# CadenceSense1_0.net
KiCad netlist of a schematic drawn in EAGLE
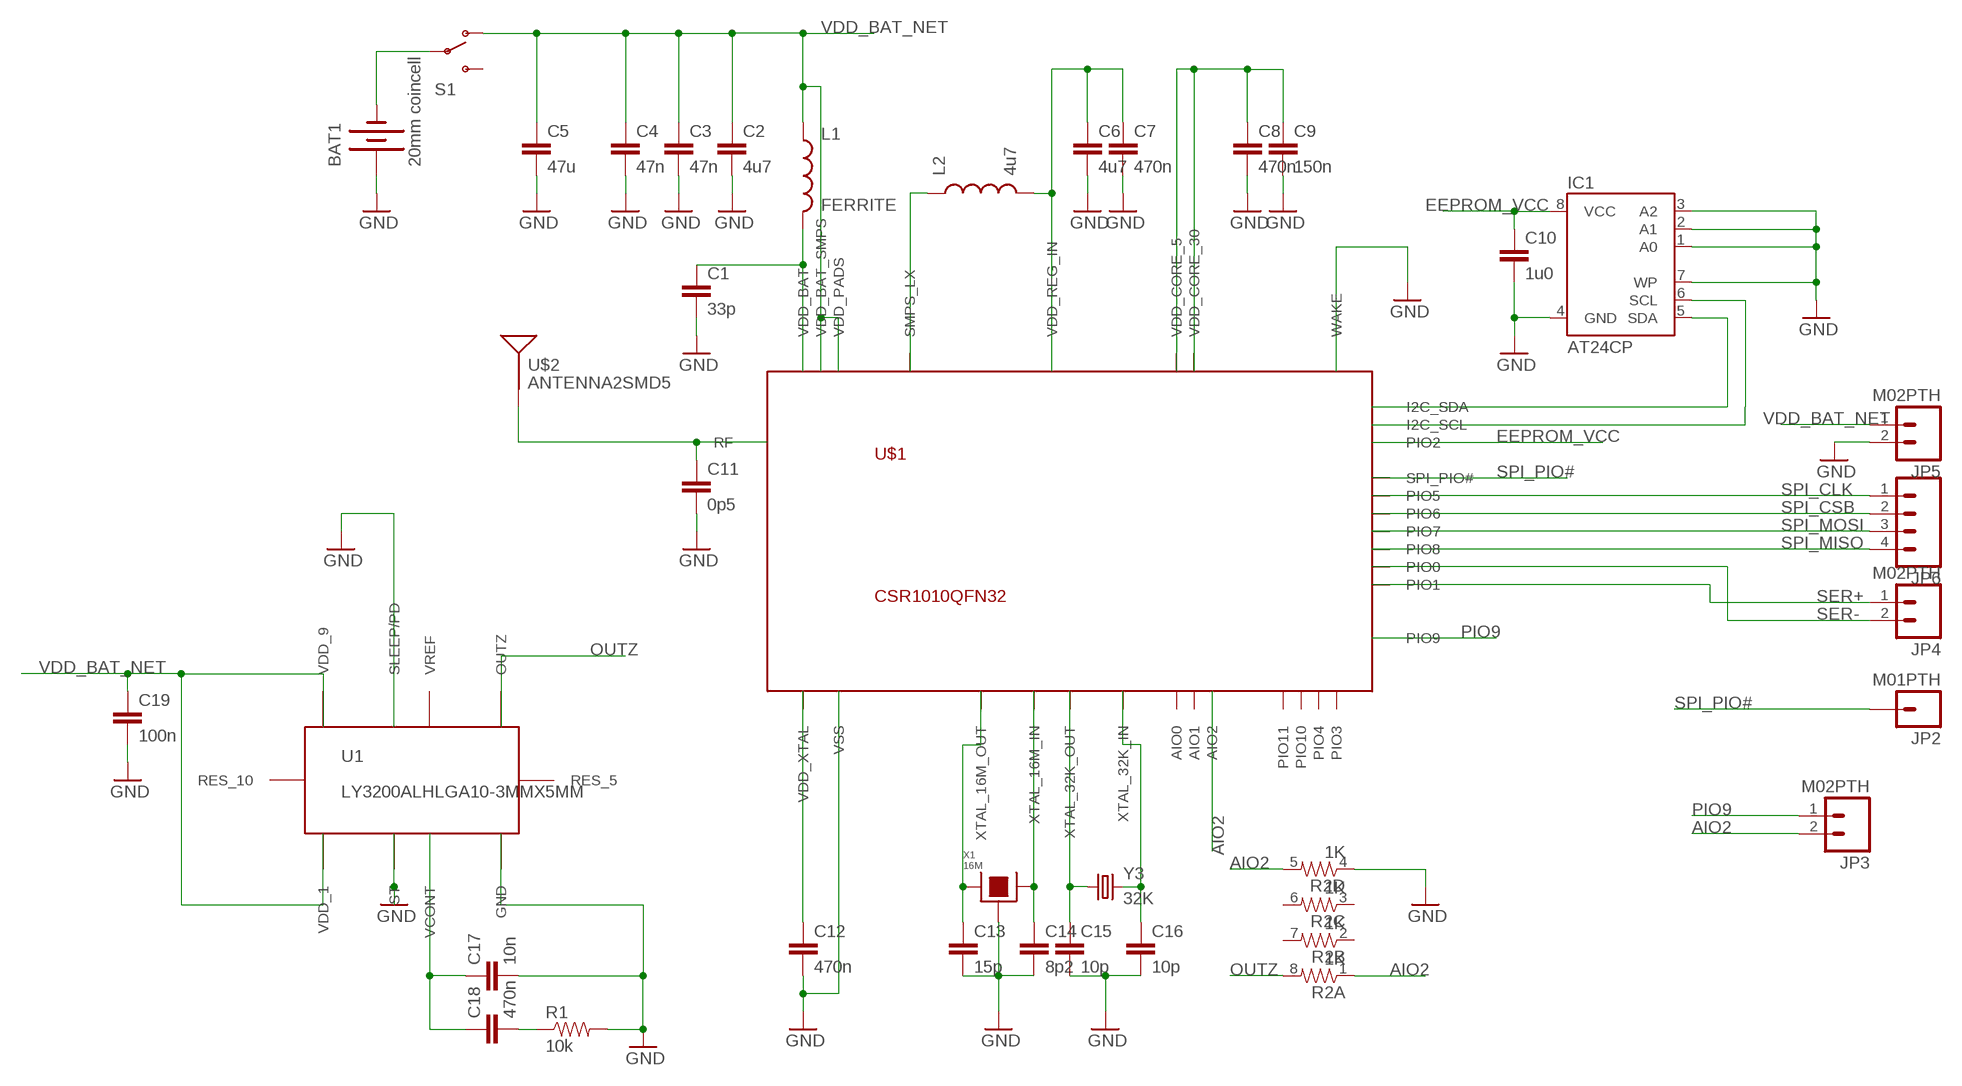
[diagram p0: schematic, sheet 1]

(export (version "E")
  (design (tool "Eeschema 10.0.6"))
  (components
    (comp (ref "BAT1")
      (value "20mm coincell")
      (footprint "eagle-import:BATTCON_20MM_4LEGS")
      (libsource (lib "eagle-import") (part "BATTERY20MM_4LEGS"))
    )
    (comp (ref "C1")
      (value "33p")
      (footprint "eagle-import:0603-CAP")
      (libsource (lib "eagle-import") (part "CAP0603-CAP"))
    )
    (comp (ref "C2")
      (value "4u7")
      (footprint "eagle-import:0603-CAP")
      (libsource (lib "eagle-import") (part "CAP0603-CAP"))
    )
    (comp (ref "C3")
      (value "47n")
      (footprint "eagle-import:0603-CAP")
      (libsource (lib "eagle-import") (part "CAP0603-CAP"))
    )
    (comp (ref "C4")
      (value "47n")
      (footprint "eagle-import:0603-CAP")
      (libsource (lib "eagle-import") (part "CAP0603-CAP"))
    )
    (comp (ref "C5")
      (value "47u")
      (footprint "eagle-import:0603-CAP")
      (libsource (lib "eagle-import") (part "CAP0603-CAP"))
    )
    (comp (ref "C6")
      (value "4u7")
      (footprint "eagle-import:0603-CAP")
      (libsource (lib "eagle-import") (part "CAP0603-CAP"))
    )
    (comp (ref "C7")
      (value "470n")
      (footprint "eagle-import:0603-CAP")
      (libsource (lib "eagle-import") (part "CAP0603-CAP"))
    )
    (comp (ref "C8")
      (value "470n")
      (footprint "eagle-import:0603-CAP")
      (libsource (lib "eagle-import") (part "CAP0603-CAP"))
    )
    (comp (ref "C9")
      (value "150n")
      (footprint "eagle-import:0603-CAP")
      (libsource (lib "eagle-import") (part "CAP0603-CAP"))
    )
    (comp (ref "C10")
      (value "1u0")
      (footprint "eagle-import:0603-CAP")
      (libsource (lib "eagle-import") (part "CAP0603-CAP"))
    )
    (comp (ref "C11")
      (value "0p5")
      (footprint "eagle-import:0603-CAP")
      (libsource (lib "eagle-import") (part "CAP0603-CAP"))
    )
    (comp (ref "C12")
      (value "470n")
      (footprint "eagle-import:0603-CAP")
      (libsource (lib "eagle-import") (part "CAP0603-CAP"))
    )
    (comp (ref "C13")
      (value "15p")
      (footprint "eagle-import:0603-CAP")
      (libsource (lib "eagle-import") (part "CAP0603-CAP"))
    )
    (comp (ref "C14")
      (value "8p2")
      (footprint "eagle-import:0603-CAP")
      (libsource (lib "eagle-import") (part "CAP0603-CAP"))
    )
    (comp (ref "C15")
      (value "10p")
      (footprint "eagle-import:0603-CAP")
      (libsource (lib "eagle-import") (part "CAP0603-CAP"))
    )
    (comp (ref "C16")
      (value "10p")
      (footprint "eagle-import:0603-CAP")
      (libsource (lib "eagle-import") (part "CAP0603-CAP"))
    )
    (comp (ref "C17")
      (value "10n")
      (footprint "eagle-import:0603-CAP")
      (libsource (lib "eagle-import") (part "CAP0603-CAP"))
    )
    (comp (ref "C18")
      (value "470n")
      (footprint "eagle-import:0603-CAP")
      (libsource (lib "eagle-import") (part "CAP0603-CAP"))
    )
    (comp (ref "C19")
      (value "100n")
      (footprint "eagle-import:0603-CAP")
      (libsource (lib "eagle-import") (part "CAP0603-CAP"))
    )
    (comp (ref "IC1")
      (value "AT24CP")
      (footprint "eagle-import:DIL08")
      (fields (field (name "MPN") "AT24C1024BW-SH-B"))
      (libsource (lib "eagle-import") (part "AT24CP"))
    )
    (comp (ref "JP2")
      (value "M01PTH")
      (footprint "eagle-import:1X01")
      (libsource (lib "eagle-import") (part "M01PTH"))
    )
    (comp (ref "JP3")
      (value "M02PTH")
      (footprint "eagle-import:1X02")
      (libsource (lib "eagle-import") (part "M02PTH"))
    )
    (comp (ref "JP4")
      (value "M02PTH")
      (footprint "eagle-import:1X02")
      (libsource (lib "eagle-import") (part "M02PTH"))
    )
    (comp (ref "JP5")
      (value "M02PTH")
      (footprint "eagle-import:1X02")
      (libsource (lib "eagle-import") (part "M02PTH"))
    )
    (comp (ref "JP6")
      (value "M04PTH")
      (footprint "eagle-import:1X04")
      (libsource (lib "eagle-import") (part "M04PTH"))
    )
    (comp (ref "L1")
      (value "FERRITE")
      (footprint "eagle-import:0805")
      (libsource (lib "eagle-import") (part "INDUCTOR0805"))
    )
    (comp (ref "L2")
      (value "4u7")
      (footprint "eagle-import:0805")
      (libsource (lib "eagle-import") (part "INDUCTOR0805"))
    )
    (comp (ref "R1")
      (value "10k")
      (footprint "eagle-import:0603-RES")
      (libsource (lib "eagle-import") (part "RESISTOR0603-RES"))
    )
    (comp (ref "R2")
      (value "1K")
      (footprint "eagle-import:0603-ARV")
      (libsource (lib "eagle-import") (part "RESISTOR-ARRAY0603-ARV"))
    )
    (comp (ref "S1")
      (value "SWITCH-SPDTPTH")
      (footprint "eagle-import:SWITCH-SPDT")
      (libsource (lib "eagle-import") (part "SWITCH-SPDTPTH"))
    )
    (comp (ref "U$1")
      (value "CSR1010QFN32")
      (footprint "eagle-import:QFN-32")
      (libsource (lib "eagle-import") (part "CSR1010QFN32"))
    )
    (comp (ref "U$2")
      (value "ANTENNA2SMD5")
      (footprint "eagle-import:ANTENNA-CHIP5")
      (libsource (lib "eagle-import") (part "ANTENNA2SMD5"))
    )
    (comp (ref "U1")
      (value "LY3200ALHLGA10-3MMX5MM")
      (footprint "eagle-import:LGA10")
      (libsource (lib "eagle-import") (part "LY3200ALHLGA10-3MMX5MM"))
    )
    (comp (ref "X1")
      (value "16M")
      (footprint "eagle-import:TSX-3225")
      (libsource (lib "eagle-import") (part "SHIELDED_CRYSTAL_TSX-3225"))
    )
    (comp (ref "Y3")
      (value "32K")
      (footprint "eagle-import:CRYSTAL-32KHZ-SMD_EPSON_MC146")
      (libsource (lib "eagle-import") (part "CRYSTALEPSONMC146"))
    )
  )
  (nets
    (net (code "1") (name "/AIO2") (class "Default")
      (node (ref "JP3") (pin "2") (pinfunction "2_2") (pintype "passive"))
      (node (ref "R2") (pin "1") (pinfunction "1_1") (pintype "passive"))
      (node (ref "R2") (pin "5") (pinfunction "2_5") (pintype "passive"))
      (node (ref "U$1") (pin "11") (pinfunction "AIO2_11") (pintype "bidirectional"))
    )
    (net (code "2") (name "/EEPROM_VCC") (class "Default")
      (node (ref "C10") (pin "1") (pinfunction "1_1") (pintype "passive"))
      (node (ref "IC1") (pin "8") (pinfunction "VCC_8") (pintype "power_in"))
      (node (ref "U$1") (pin "27") (pinfunction "PIO2_27") (pintype "bidirectional"))
    )
    (net (code "3") (name "/OUTZ") (class "Default")
      (node (ref "R2") (pin "8") (pinfunction "2_8") (pintype "passive"))
      (node (ref "U1") (pin "6") (pinfunction "OUTZ_6") (pintype "bidirectional"))
    )
    (net (code "4") (name "/PIO9") (class "Default")
      (node (ref "JP3") (pin "1") (pinfunction "1_1") (pintype "passive"))
      (node (ref "U$1") (pin "23") (pinfunction "PIO9_23") (pintype "bidirectional"))
    )
    (net (code "5") (name "/SER+") (class "Default")
      (node (ref "JP4") (pin "1") (pinfunction "1_1") (pintype "passive"))
      (node (ref "U$1") (pin "15") (pinfunction "PIO1_15") (pintype "bidirectional"))
    )
    (net (code "6") (name "/SER-") (class "Default")
      (node (ref "JP4") (pin "2") (pinfunction "2_2") (pintype "passive"))
      (node (ref "U$1") (pin "14") (pinfunction "PIO0_14") (pintype "bidirectional"))
    )
    (net (code "7") (name "/SPI_CLK") (class "Default")
      (node (ref "JP6") (pin "1") (pinfunction "1_1") (pintype "passive"))
      (node (ref "U$1") (pin "18") (pinfunction "PIO5_18") (pintype "bidirectional"))
    )
    (net (code "8") (name "/SPI_CSB") (class "Default")
      (node (ref "JP6") (pin "2") (pinfunction "2_2") (pintype "passive"))
      (node (ref "U$1") (pin "19") (pinfunction "PIO6_19") (pintype "bidirectional"))
    )
    (net (code "9") (name "/SPI_MISO") (class "Default")
      (node (ref "JP6") (pin "4") (pinfunction "4_4") (pintype "passive"))
      (node (ref "U$1") (pin "22") (pinfunction "PIO8_22") (pintype "bidirectional"))
    )
    (net (code "10") (name "/SPI_MOSI") (class "Default")
      (node (ref "JP6") (pin "3") (pinfunction "3_3") (pintype "passive"))
      (node (ref "U$1") (pin "20") (pinfunction "PIO7_20") (pintype "bidirectional"))
    )
    (net (code "11") (name "/SPI_PIO#") (class "Default")
      (node (ref "JP2") (pin "1") (pinfunction "1_1") (pintype "passive"))
      (node (ref "U$1") (pin "26") (pinfunction "SPI_PIO#_26") (pintype "bidirectional"))
    )
    (net (code "12") (name "/VDD_BAT_NET") (class "Default")
      (node (ref "C19") (pin "1") (pinfunction "1_1") (pintype "passive"))
      (node (ref "C2") (pin "1") (pinfunction "1_1") (pintype "passive"))
      (node (ref "C3") (pin "1") (pinfunction "1_1") (pintype "passive"))
      (node (ref "C4") (pin "1") (pinfunction "1_1") (pintype "passive"))
      (node (ref "C5") (pin "1") (pinfunction "1_1") (pintype "passive"))
      (node (ref "JP5") (pin "1") (pinfunction "1_1") (pintype "passive"))
      (node (ref "L1") (pin "1") (pinfunction "1_1") (pintype "passive"))
      (node (ref "S1") (pin "1") (pinfunction "O_1") (pintype "passive"))
      (node (ref "U$1") (pin "21") (pinfunction "VDD_PADS_21") (pintype "power_in"))
      (node (ref "U$1") (pin "32") (pinfunction "VDD_BAT_SMPS_32") (pintype "power_in"))
      (node (ref "U1") (pin "1") (pinfunction "VDD_1_1") (pintype "power_in"))
      (node (ref "U1") (pin "9") (pinfunction "VDD_9_9") (pintype "power_in"))
    )
    (net (code "13") (name "GND") (class "Default")
      (node (ref "BAT1") (pin "1") (pinfunction "+_1") (pintype "power_in"))
      (node (ref "C1") (pin "2") (pinfunction "2_2") (pintype "passive"))
      (node (ref "C10") (pin "2") (pinfunction "2_2") (pintype "passive"))
      (node (ref "C11") (pin "2") (pinfunction "2_2") (pintype "passive"))
      (node (ref "C12") (pin "2") (pinfunction "2_2") (pintype "passive"))
      (node (ref "C13") (pin "2") (pinfunction "2_2") (pintype "passive"))
      (node (ref "C14") (pin "2") (pinfunction "2_2") (pintype "passive"))
      (node (ref "C15") (pin "2") (pinfunction "2_2") (pintype "passive"))
      (node (ref "C16") (pin "2") (pinfunction "2_2") (pintype "passive"))
      (node (ref "C17") (pin "2") (pinfunction "2_2") (pintype "passive"))
      (node (ref "C19") (pin "2") (pinfunction "2_2") (pintype "passive"))
      (node (ref "C2") (pin "2") (pinfunction "2_2") (pintype "passive"))
      (node (ref "C3") (pin "2") (pinfunction "2_2") (pintype "passive"))
      (node (ref "C4") (pin "2") (pinfunction "2_2") (pintype "passive"))
      (node (ref "C5") (pin "2") (pinfunction "2_2") (pintype "passive"))
      (node (ref "C6") (pin "2") (pinfunction "2_2") (pintype "passive"))
      (node (ref "C7") (pin "2") (pinfunction "2_2") (pintype "passive"))
      (node (ref "C8") (pin "2") (pinfunction "2_2") (pintype "passive"))
      (node (ref "C9") (pin "2") (pinfunction "2_2") (pintype "passive"))
      (node (ref "IC1") (pin "1") (pinfunction "A0_1") (pintype "input"))
      (node (ref "IC1") (pin "2") (pinfunction "A1_2") (pintype "input"))
      (node (ref "IC1") (pin "3") (pinfunction "A2_3") (pintype "input"))
      (node (ref "IC1") (pin "4") (pinfunction "GND_4") (pintype "power_in"))
      (node (ref "IC1") (pin "7") (pinfunction "WP_7") (pintype "input"))
      (node (ref "JP5") (pin "2") (pinfunction "2_2") (pintype "passive"))
      (node (ref "R1") (pin "2") (pinfunction "2_2") (pintype "passive"))
      (node (ref "R2") (pin "4") (pinfunction "1_4") (pintype "passive"))
      (node (ref "U$1") (pin "4") (pinfunction "WAKE_4") (pintype "bidirectional"))
      (node (ref "U$1") (pin "EP") (pinfunction "VSS_EP") (pintype "power_in"))
      (node (ref "U1") (pin "2") (pinfunction "ST_2") (pintype "input"))
      (node (ref "U1") (pin "4") (pinfunction "GND_4") (pintype "power_in"))
      (node (ref "U1") (pin "8") (pinfunction "SLEEP/PD_8") (pintype "input"))
      (node (ref "X1") (pin "2") (pinfunction "P$3_2") (pintype "bidirectional"))
      (node (ref "X1") (pin "4") (pinfunction "P$3_4") (pintype "bidirectional"))
    )
    (net (code "14") (name "Net-(BAT1--)") (class "Default")
      (node (ref "BAT1") (pin "2") (pinfunction "-_2") (pintype "power_in"))
      (node (ref "S1") (pin "2") (pinfunction "P_2") (pintype "passive"))
    )
    (net (code "15") (name "Net-(C18-Pad2)") (class "Default")
      (node (ref "C18") (pin "2") (pinfunction "2_2") (pintype "passive"))
      (node (ref "R1") (pin "1") (pinfunction "1_1") (pintype "passive"))
    )
    (net (code "16") (name "Net-(IC1-SCL)") (class "Default")
      (node (ref "IC1") (pin "6") (pinfunction "SCL_6") (pintype "bidirectional"))
      (node (ref "U$1") (pin "28") (pinfunction "I2C_SCL_28") (pintype "bidirectional"))
    )
    (net (code "17") (name "Net-(IC1-SDA)") (class "Default")
      (node (ref "IC1") (pin "5") (pinfunction "SDA_5") (pintype "bidirectional"))
      (node (ref "U$1") (pin "29") (pinfunction "I2C_SDA_29") (pintype "bidirectional"))
    )
    (net (code "18") (name "Net-(U$1-RF)") (class "Default")
      (node (ref "C11") (pin "1") (pinfunction "1_1") (pintype "passive"))
      (node (ref "U$1") (pin "7") (pinfunction "RF_7") (pintype "bidirectional"))
      (node (ref "U$2") (pin "FEED") (pinfunction "SIGNAL_FEED") (pintype "bidirectional"))
    )
    (net (code "19") (name "Net-(U$1-SMPS_LX)") (class "Default")
      (node (ref "L2") (pin "1") (pinfunction "1_1") (pintype "passive"))
      (node (ref "U$1") (pin "31") (pinfunction "SMPS_LX_31") (pintype "power_in"))
    )
    (net (code "20") (name "Net-(U$1-VDD_BAT)") (class "Default")
      (node (ref "C1") (pin "1") (pinfunction "1_1") (pintype "passive"))
      (node (ref "L1") (pin "2") (pinfunction "2_2") (pintype "passive"))
      (node (ref "U$1") (pin "1") (pinfunction "VDD_BAT_1") (pintype "power_in"))
    )
    (net (code "21") (name "Net-(U$1-VDD_CORE_30)") (class "Default")
      (node (ref "C8") (pin "1") (pinfunction "1_1") (pintype "passive"))
      (node (ref "C9") (pin "1") (pinfunction "1_1") (pintype "passive"))
      (node (ref "U$1") (pin "30") (pinfunction "VDD_CORE_30_30") (pintype "power_in"))
      (node (ref "U$1") (pin "5") (pinfunction "VDD_CORE_5_5") (pintype "power_in"))
    )
    (net (code "22") (name "Net-(U$1-VDD_REG_IN)") (class "Default")
      (node (ref "C6") (pin "1") (pinfunction "1_1") (pintype "passive"))
      (node (ref "C7") (pin "1") (pinfunction "1_1") (pintype "passive"))
      (node (ref "L2") (pin "2") (pinfunction "2_2") (pintype "passive"))
      (node (ref "U$1") (pin "6") (pinfunction "VDD_REG_IN_6") (pintype "power_in"))
    )
    (net (code "23") (name "Net-(U$1-VDD_XTAL)") (class "Default")
      (node (ref "C12") (pin "1") (pinfunction "1_1") (pintype "passive"))
      (node (ref "U$1") (pin "8") (pinfunction "VDD_XTAL_8") (pintype "bidirectional"))
    )
    (net (code "24") (name "Net-(U$1-XTAL_16M_IN)") (class "Default")
      (node (ref "C14") (pin "1") (pinfunction "1_1") (pintype "passive"))
      (node (ref "U$1") (pin "10") (pinfunction "XTAL_16M_IN_10") (pintype "bidirectional"))
      (node (ref "X1") (pin "3") (pinfunction "P$2_3") (pintype "bidirectional"))
    )
    (net (code "25") (name "Net-(U$1-XTAL_16M_OUT)") (class "Default")
      (node (ref "C13") (pin "1") (pinfunction "1_1") (pintype "passive"))
      (node (ref "U$1") (pin "9") (pinfunction "XTAL_16M_OUT_9") (pintype "bidirectional"))
      (node (ref "X1") (pin "1") (pinfunction "P$1_1") (pintype "bidirectional"))
    )
    (net (code "26") (name "Net-(U$1-XTAL_32K_IN)") (class "Default")
      (node (ref "C16") (pin "1") (pinfunction "1_1") (pintype "passive"))
      (node (ref "U$1") (pin "3") (pinfunction "XTAL_32K_IN_3") (pintype "bidirectional"))
      (node (ref "Y3") (pin "P$1") (pinfunction "2_P$1") (pintype "passive"))
    )
    (net (code "27") (name "Net-(U$1-XTAL_32K_OUT)") (class "Default")
      (node (ref "C15") (pin "1") (pinfunction "1_1") (pintype "passive"))
      (node (ref "U$1") (pin "2") (pinfunction "XTAL_32K_OUT_2") (pintype "bidirectional"))
      (node (ref "Y3") (pin "P$2") (pinfunction "1_P$2") (pintype "passive"))
    )
    (net (code "28") (name "Net-(U1-VCONT)") (class "Default")
      (node (ref "C17") (pin "1") (pinfunction "1_1") (pintype "passive"))
      (node (ref "C18") (pin "1") (pinfunction "1_1") (pintype "passive"))
      (node (ref "U1") (pin "3") (pinfunction "VCONT_3") (pintype "bidirectional"))
    )
    (net (code "29") (name "unconnected-(R2B-1-Pad2)") (class "Default")
      (node (ref "R2") (pin "2") (pinfunction "1_2") (pintype "passive"))
    )
    (net (code "30") (name "unconnected-(R2B-2-Pad7)") (class "Default")
      (node (ref "R2") (pin "7") (pinfunction "2_7") (pintype "passive"))
    )
    (net (code "31") (name "unconnected-(R2C-1-Pad3)") (class "Default")
      (node (ref "R2") (pin "3") (pinfunction "1_3") (pintype "passive"))
    )
    (net (code "32") (name "unconnected-(R2C-2-Pad6)") (class "Default")
      (node (ref "R2") (pin "6") (pinfunction "2_6") (pintype "passive"))
    )
    (net (code "33") (name "unconnected-(S1-S-Pad3)") (class "Default")
      (node (ref "S1") (pin "3") (pinfunction "S_3") (pintype "passive"))
    )
    (net (code "34") (name "unconnected-(U$1-AIO0-Pad13)") (class "Default")
      (node (ref "U$1") (pin "13") (pinfunction "AIO0_13") (pintype "bidirectional"))
    )
    (net (code "35") (name "unconnected-(U$1-AIO1-Pad12)") (class "Default")
      (node (ref "U$1") (pin "12") (pinfunction "AIO1_12") (pintype "bidirectional"))
    )
    (net (code "36") (name "unconnected-(U$1-PIO3-Pad16)") (class "Default")
      (node (ref "U$1") (pin "16") (pinfunction "PIO3_16") (pintype "bidirectional"))
    )
    (net (code "37") (name "unconnected-(U$1-PIO4-Pad17)") (class "Default")
      (node (ref "U$1") (pin "17") (pinfunction "PIO4_17") (pintype "bidirectional"))
    )
    (net (code "38") (name "unconnected-(U$1-PIO10-Pad24)") (class "Default")
      (node (ref "U$1") (pin "24") (pinfunction "PIO10_24") (pintype "bidirectional"))
    )
    (net (code "39") (name "unconnected-(U$1-PIO11-Pad25)") (class "Default")
      (node (ref "U$1") (pin "25") (pinfunction "PIO11_25") (pintype "bidirectional"))
    )
    (net (code "40") (name "unconnected-(U1-RES_5-Pad5)") (class "Default")
      (node (ref "U1") (pin "5") (pinfunction "RES_5_5") (pintype "no_connect"))
    )
    (net (code "41") (name "unconnected-(U1-RES_10-Pad10)") (class "Default")
      (node (ref "U1") (pin "10") (pinfunction "RES_10_10") (pintype "no_connect"))
    )
    (net (code "42") (name "unconnected-(U1-VREF-Pad7)") (class "Default")
      (node (ref "U1") (pin "7") (pinfunction "VREF_7") (pintype "output"))
    )
  )
)
